# 06_IN_OUT_SENSOR.net
KiCad netlist of a schematic drawn in Altium Designer
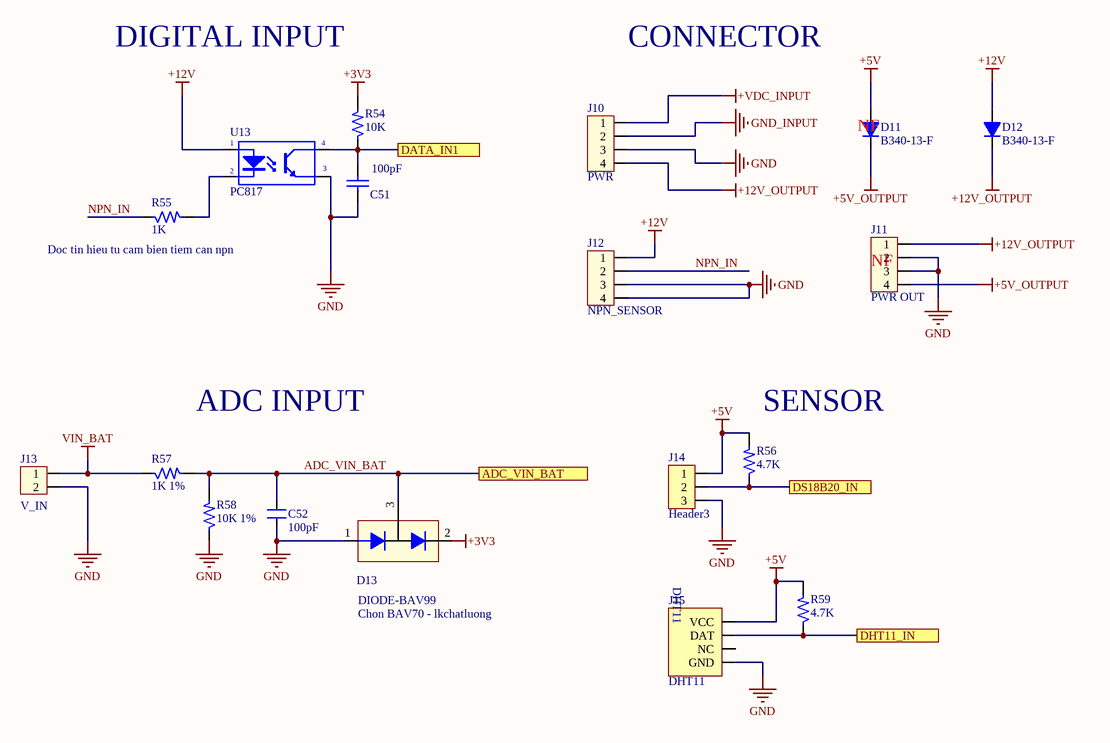
[diagram p0: [06] IN_OUT_SENSOR.SchDoc]

(export (version "E")
  (design (tool "Eeschema 10.0.6"))
  (components
    (comp (ref "C51")
      (value "100pF")
      (footprint "CAP_0805")
      (description "Capacitor")
      (fields (field (name "PUBLISHER") "Altium Limited"))
      (libsource (lib "My Library") (part "CapSMD"))
    )
    (comp (ref "C52")
      (value "100pF")
      (footprint "CAP_0805")
      (description "Cap SMD")
      (libsource (lib "khapham") (part "CM"))
    )
    (comp (ref "D11")
      (value "B340-13-F")
      (footprint "DO-214AB SMA")
      (description "Diode 1A")
      (libsource (lib "GPS_Traking_V1_1") (part "D1A"))
    )
    (comp (ref "D12")
      (value "B340-13-F")
      (footprint "DO-214AB SMA")
      (description "Diode 1A")
      (libsource (lib "GPS_Traking_V1_1") (part "D1A"))
    )
    (comp (ref "D13")
      (value "DIODE-BAV99")
      (footprint "SOT23")
      (description "ZENER, SOT23,")
      (fields
        (field (name "MANUFACTURER") "ON Semiconductor / Fairchild")
        (field (name "MANUFACTURER PART NUMBER") "BAV99")
        (field (name ".CREATOR") "LeKhaLinh")
        (field (name ".CHECKPCB") "LeKhaLinh")
        (field (name ".CHECKSCH") "LeKhaLinh")
      )
      (libsource (lib "GPS_Traking_V1_1") (part "DIODE-BAV99"))
    )
    (comp (ref "J10")
      (value "PWR")
      (footprint "Hed4V_3.96")
      (description "Header 4 (Green)")
      (libsource (lib "GPS_Traking_V1_1") (part "Hed4"))
    )
    (comp (ref "J11")
      (value "PWR OUT")
      (footprint "CON_2.54mm_4")
      (description "Connector 4")
      (libsource (lib "GPS_Traking_V1_1") (part "Con4"))
    )
    (comp (ref "J12")
      (value "NPN_SENSOR")
      (footprint "CON_2.54mm_4")
      (description "Connector 4")
      (libsource (lib "GPS_Traking_V1_1") (part "Con4"))
    )
    (comp (ref "J13")
      (value "V_IN")
      (footprint "CON_2.54mm_2")
      (description "Connector 2")
      (libsource (lib "khapham") (part "Con2"))
    )
    (comp (ref "J14")
      (value "Header3")
      (footprint "Header3")
      (description "Header IDC, 3 x 1 Pin Vertical 2.54mm Pitch (Non-Boxed, Male)")
      (fields
        (field (name "MANUFACTURER") "Würth Elektronik eiSos GmbH")
        (field (name "PARTNO") "613002143121")
        (field (name "CREATED BY") "Karrer Zheng")
      )
      (libsource (lib "My Library") (part "Header3"))
    )
    (comp (ref "J15")
      (value "DHT11")
      (footprint "DHT11")
      (fields
        (field (name "MANUFACTURER") "Würth Elektronik eiSos GmbH")
        (field (name "PARTNO") "613004143121")
        (field (name "CREATED BY") "Karrer Zheng")
      )
      (libsource (lib "My Library") (part "DHT11"))
    )
    (comp (ref "R54")
      (value "10K")
      (footprint "RES-SMD-0805")
      (description "Resistor SMD")
      (libsource (lib "khapham") (part "RM"))
    )
    (comp (ref "R55")
      (value "1K")
      (footprint "RES-SMD-0805")
      (description "Resistor SMD")
      (libsource (lib "khapham") (part "RM"))
    )
    (comp (ref "R56")
      (value "4.7K")
      (footprint "RES-SMD-0805")
      (description "Resistor SMD")
      (libsource (lib "khapham") (part "RM"))
    )
    (comp (ref "R57")
      (value "1K 1%")
      (footprint "RES-SMD-0805")
      (description "Resistor SMD")
      (libsource (lib "khapham") (part "RM"))
    )
    (comp (ref "R58")
      (value "10K 1%")
      (footprint "RES-SMD-0805")
      (description "Resistor SMD")
      (libsource (lib "khapham") (part "RM"))
    )
    (comp (ref "R59")
      (value "4.7K")
      (footprint "RES-SMD-0805")
      (description "Resistor SMD")
      (libsource (lib "khapham") (part "RM"))
    )
    (comp (ref "U13")
      (value "PC817")
      (footprint "DIP4/W0.3")
      (description "Single Opto")
      (libsource (lib "GPS_Traking_V1_1") (part "PC817"))
    )
  )
  (nets
    (net (code "1") (name "+3V3") (class "Default")
      (node (ref "D13") (pin "2") (pinfunction "2_2") (pintype "passive"))
      (node (ref "R54") (pin "2") (pinfunction "2_2") (pintype "passive"))
    )
    (net (code "2") (name "+5V") (class "Default")
      (node (ref "D11") (pin "1") (pinfunction "A_1") (pintype "passive"))
      (node (ref "J14") (pin "1") (pinfunction "1_1") (pintype "passive"))
      (node (ref "J15") (pin "1") (pinfunction "VCC_1") (pintype "passive"))
      (node (ref "R56") (pin "2") (pinfunction "2_2") (pintype "passive"))
      (node (ref "R59") (pin "2") (pinfunction "2_2") (pintype "passive"))
    )
    (net (code "3") (name "+5V_OUTPUT") (class "Default")
      (node (ref "D11") (pin "2") (pinfunction "K_2") (pintype "passive"))
      (node (ref "J11") (pin "4") (pinfunction "4_4") (pintype "passive"))
    )
    (net (code "4") (name "+12V") (class "Default")
      (node (ref "D12") (pin "1") (pinfunction "A_1") (pintype "passive"))
      (node (ref "J12") (pin "1") (pinfunction "1_1") (pintype "passive"))
      (node (ref "U13") (pin "1") (pinfunction "A_1") (pintype "passive"))
    )
    (net (code "5") (name "+12V_OUTPUT") (class "Default")
      (node (ref "D12") (pin "2") (pinfunction "K_2") (pintype "passive"))
      (node (ref "J10") (pin "4") (pinfunction "4_4") (pintype "passive"))
      (node (ref "J11") (pin "1") (pinfunction "1_1") (pintype "passive"))
    )
    (net (code "6") (name "+VDC_INPUT") (class "Default")
      (node (ref "J10") (pin "1") (pinfunction "1_1") (pintype "passive"))
    )
    (net (code "7") (name "/ADC_VIN_BAT") (class "Default")
      (node (ref "C52") (pin "2") (pinfunction "2_2") (pintype "passive"))
      (node (ref "D13") (pin "3") (pinfunction "3_3") (pintype "passive"))
      (node (ref "R57") (pin "2") (pinfunction "2_2") (pintype "passive"))
      (node (ref "R58") (pin "2") (pinfunction "2_2") (pintype "passive"))
    )
    (net (code "8") (name "/DATA_IN1") (class "Default")
      (node (ref "C51") (pin "1") (pinfunction "1_1") (pintype "passive"))
      (node (ref "R54") (pin "1") (pinfunction "1_1") (pintype "passive"))
      (node (ref "U13") (pin "4") (pinfunction "C_4") (pintype "passive"))
    )
    (net (code "9") (name "/DHT11_IN") (class "Default")
      (node (ref "J15") (pin "2") (pinfunction "DAT_2") (pintype "passive"))
      (node (ref "R59") (pin "1") (pinfunction "1_1") (pintype "passive"))
    )
    (net (code "10") (name "/DS18B20_IN") (class "Default")
      (node (ref "J14") (pin "2") (pinfunction "2_2") (pintype "passive"))
      (node (ref "R56") (pin "1") (pinfunction "1_1") (pintype "passive"))
    )
    (net (code "11") (name "/NPN_IN") (class "Default")
      (node (ref "J12") (pin "2") (pinfunction "2_2") (pintype "passive"))
      (node (ref "R55") (pin "1") (pinfunction "1_1") (pintype "passive"))
    )
    (net (code "12") (name "GND") (class "Default")
      (node (ref "C51") (pin "2") (pinfunction "2_2") (pintype "passive"))
      (node (ref "C52") (pin "1") (pinfunction "1_1") (pintype "passive"))
      (node (ref "D13") (pin "1") (pinfunction "1_1") (pintype "passive"))
      (node (ref "J10") (pin "3") (pinfunction "3_3") (pintype "passive"))
      (node (ref "J11") (pin "2") (pinfunction "2_2") (pintype "passive"))
      (node (ref "J11") (pin "3") (pinfunction "3_3") (pintype "passive"))
      (node (ref "J12") (pin "3") (pinfunction "3_3") (pintype "passive"))
      (node (ref "J12") (pin "4") (pinfunction "4_4") (pintype "passive"))
      (node (ref "J13") (pin "2") (pinfunction "2_2") (pintype "passive"))
      (node (ref "J14") (pin "3") (pinfunction "3_3") (pintype "passive"))
      (node (ref "J15") (pin "4") (pinfunction "GND_4") (pintype "passive"))
      (node (ref "R58") (pin "1") (pinfunction "1_1") (pintype "passive"))
      (node (ref "U13") (pin "3") (pinfunction "E_3") (pintype "passive"))
    )
    (net (code "13") (name "GND_INPUT") (class "Default")
      (node (ref "J10") (pin "2") (pinfunction "2_2") (pintype "passive"))
    )
    (net (code "14") (name "Net-(U13-K)") (class "Default")
      (node (ref "R55") (pin "2") (pinfunction "2_2") (pintype "passive"))
      (node (ref "U13") (pin "2") (pinfunction "K_2") (pintype "passive"))
    )
    (net (code "15") (name "VIN_BAT") (class "Default")
      (node (ref "J13") (pin "1") (pinfunction "1_1") (pintype "passive"))
      (node (ref "R57") (pin "1") (pinfunction "1_1") (pintype "passive"))
    )
    (net (code "16") (name "unconnected-(J15-NC-Pad3)") (class "Default")
      (node (ref "J15") (pin "3") (pinfunction "NC_3") (pintype "passive"))
    )
  )
)
